# LCD-Battery.net
KiCad netlist of a schematic drawn in Altium Designer
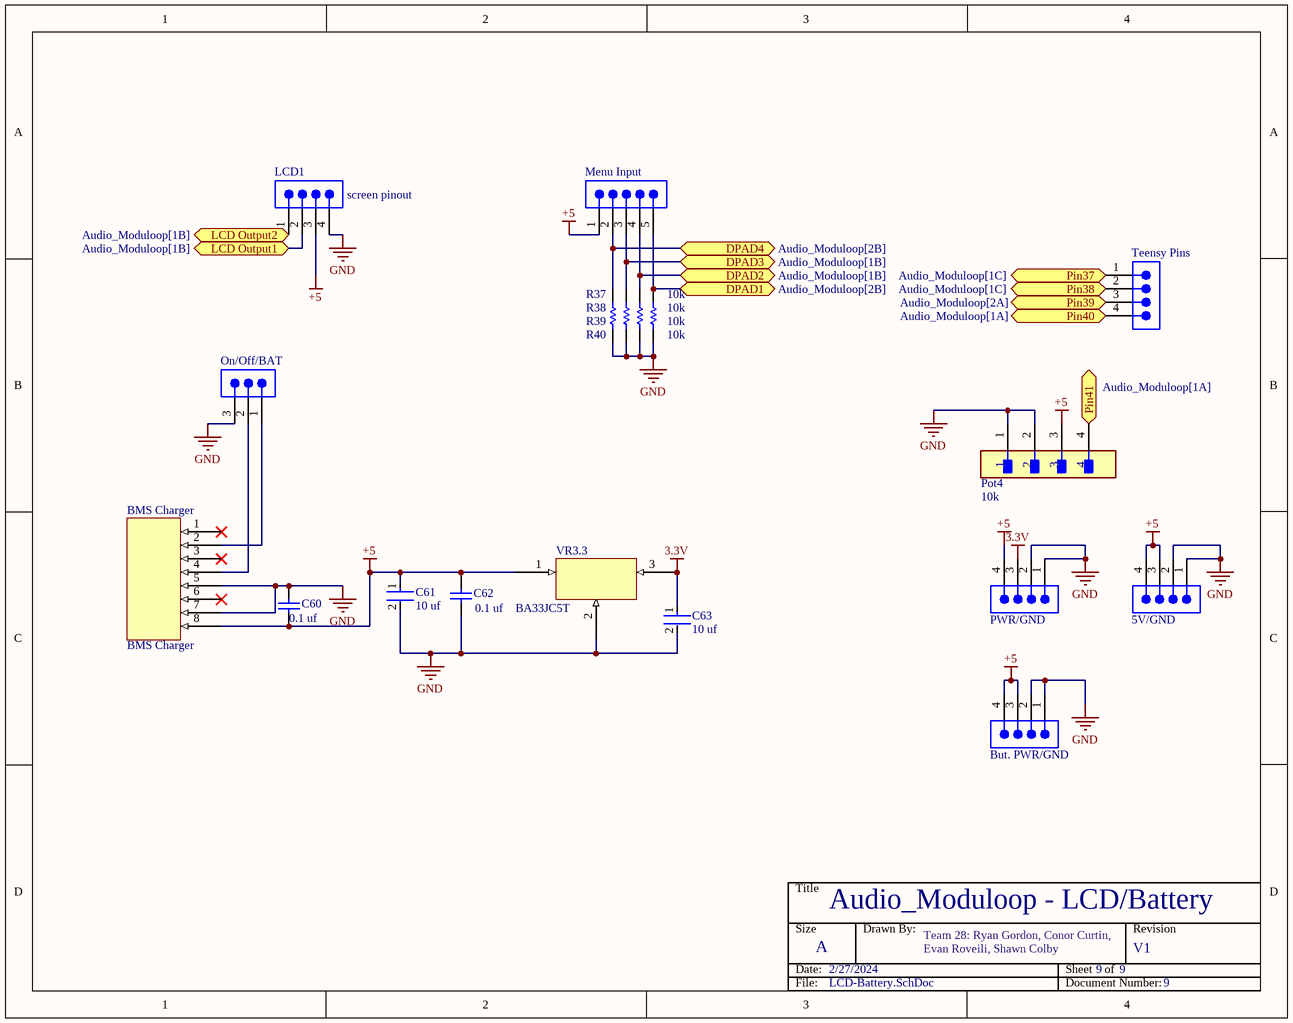
[diagram p0: LCD-Battery.SchDoc]

(export (version "E")
  (design (tool "Eeschema 10.0.6"))
  (components
    (comp (ref "5V/GND")
      (value "61300411121")
      (footprint "61300411121")
      (libsource (lib "Altium Content Vault") (part "Header_Male_1R_04P"))
    )
    (comp (ref "BMS Charger")
      (value "BMS Charger")
      (footprint "MODULE_2465")
      (description "Holder Battery; AA Battery; 3 Cells; 6 in. Wire Lead; Chassis Mount; Polypropylene")
      (libsource (lib "Ryamgordon") (part "Charger"))
    )
    (comp (ref "But. PWR/GND")
      (value "61300411121")
      (footprint "61300411121")
      (libsource (lib "Altium Content Vault") (part "Header_Male_1R_04P"))
    )
    (comp (ref "C60")
      (value "0.1 uf")
      (footprint "AVX-SA115C104KAR")
      (fields (field (name "TOLERANCE") "±10%") (field (name "MANUFACTURER") "AVX"))
      (libsource (lib "Altium Content Vault") (part "CAP-NP-2"))
    )
    (comp (ref "C61")
      (value "10 uf")
      (footprint "FP-RCE3DB-MFG")
      (description "Cap Ceramic 10uF 25V X7R ±10% Radial 2.5mm +125°C Automotive Ammo Pack")
      (fields (field (name "TOLERANCE") "10%"))
      (libsource (lib "Altium Content Vault") (part "b4654b650e69147ec39a6b967a45e02"))
    )
    (comp (ref "C62")
      (value "0.1 uf")
      (footprint "AVX-SA115C104KAR")
      (fields (field (name "TOLERANCE") "±10%") (field (name "MANUFACTURER") "AVX"))
      (libsource (lib "Altium Content Vault") (part "CAP-NP-2"))
    )
    (comp (ref "C63")
      (value "10 uf")
      (footprint "FP-RCE3DB-MFG")
      (description "Cap Ceramic 10uF 25V X7R ±10% Radial 2.5mm +125°C Automotive Ammo Pack")
      (fields (field (name "TOLERANCE") "10%"))
      (libsource (lib "Altium Content Vault") (part "b4654b650e69147ec39a6b967a45e02"))
    )
    (comp (ref "LCD1")
      (value "screen pinout")
      (footprint "61900411121")
      (libsource (lib "Altium Content Vault") (part "Header_Male_1R_04P"))
    )
    (comp (ref "Menu Input")
      (value "61300511121")
      (footprint "61300511121")
      (libsource (lib "Altium Content Vault") (part "Header_Male_1R_05P"))
    )
    (comp (ref "On/Off/BAT")
      (value "TSW-103-07-F-S")
      (footprint "SMTC-TSW-103-07-X-S")
      (description "0.025\" SQ Post Header, Through-hole, Vertical, -55 to 125 degC, 2.54 mm Pitch, 3-Pin, Male, RoHS")
      (fields (field (name "MANUFACTURER") "Samtec"))
      (libsource (lib "Altium Content Vault") (part "SMTC-TSW-103-X-X-S-X"))
    )
    (comp (ref "Pot4")
      (value "10k")
      (footprint "FP-B4B-XH-A_LF_SN-MFG")
      (description "CONN HEADER VERT 4POS 2.5MM")
      (libsource (lib "Altium Content Vault") (part "299a8cea1bdcbc3624fe62c390fa72c"))
    )
    (comp (ref "PWR/GND")
      (value "61300411121")
      (footprint "61300411121")
      (libsource (lib "Altium Content Vault") (part "Header_Male_1R_04P"))
    )
    (comp (ref "R37")
      (value "10k")
      (footprint "RESC2013X60X35NL10T20")
      (description "Chip Resistor, 10 KOhm, +/- 1%, 0.125 W, -55 to 155 degC, 0805 (2012 Metric), RoHS, Tape and Reel")
      (fields (field (name "MANUFACTURER") "Yageo"))
      (libsource (lib "Altium Content Vault") (part "RES-2"))
    )
    (comp (ref "R38")
      (value "10k")
      (footprint "RESC2013X60X35NL10T20")
      (description "Chip Resistor, 10 KOhm, +/- 1%, 0.125 W, -55 to 155 degC, 0805 (2012 Metric), RoHS, Tape and Reel")
      (fields (field (name "MANUFACTURER") "Yageo"))
      (libsource (lib "Altium Content Vault") (part "RES-2"))
    )
    (comp (ref "R39")
      (value "10k")
      (footprint "RESC2013X60X35NL10T20")
      (description "Chip Resistor, 10 KOhm, +/- 1%, 0.125 W, -55 to 155 degC, 0805 (2012 Metric), RoHS, Tape and Reel")
      (fields (field (name "MANUFACTURER") "Yageo"))
      (libsource (lib "Altium Content Vault") (part "RES-2"))
    )
    (comp (ref "R40")
      (value "10k")
      (footprint "RESC2013X60X35NL10T20")
      (description "Chip Resistor, 10 KOhm, +/- 1%, 0.125 W, -55 to 155 degC, 0805 (2012 Metric), RoHS, Tape and Reel")
      (fields (field (name "MANUFACTURER") "Yageo"))
      (libsource (lib "Altium Content Vault") (part "RES-2"))
    )
    (comp (ref "Teensy Pins")
      (value "61300411121")
      (footprint "61300411121")
      (libsource (lib "Altium Content Vault") (part "Header_Male_1R_04P"))
    )
    (comp (ref "VR3.3")
      (value "BA33JC5T")
      (footprint "TO254P1030X480X2260-3")
      (description "Fixed Positive LDO Regulator, 3.3V, 0.5V Dropout, BIPolar")
      (libsource (lib "Ryamgordon") (part "BA33JC5T-Symbol-1"))
    )
  )
  (nets
    (net (code "1") (name "+5") (class "Default")
      (node (ref "5V/GND") (pin "3") (pinfunction "3_3") (pintype "passive"))
      (node (ref "5V/GND") (pin "4") (pinfunction "4_4") (pintype "passive"))
      (node (ref "BMS Charger") (pin "8") (pintype "input"))
      (node (ref "But. PWR/GND") (pin "3") (pinfunction "3_3") (pintype "passive"))
      (node (ref "But. PWR/GND") (pin "4") (pinfunction "4_4") (pintype "passive"))
      (node (ref "C60") (pin "1") (pinfunction "1_1") (pintype "passive"))
      (node (ref "C61") (pin "1") (pinfunction "1_1") (pintype "passive"))
      (node (ref "C62") (pin "2") (pinfunction "2_2") (pintype "passive"))
      (node (ref "LCD1") (pin "3") (pinfunction "3_3") (pintype "passive"))
      (node (ref "Menu Input") (pin "1") (pinfunction "1_1") (pintype "passive"))
      (node (ref "PWR/GND") (pin "4") (pinfunction "4_4") (pintype "passive"))
      (node (ref "Pot4") (pin "3") (pinfunction "3_3") (pintype "passive"))
      (node (ref "VR3.3") (pin "1") (pintype "input"))
    )
    (net (code "2") (name "/DPAD1") (class "Default")
      (node (ref "Menu Input") (pin "5") (pinfunction "5_5") (pintype "passive"))
      (node (ref "R40") (pin "1") (pinfunction "1_1") (pintype "passive"))
    )
    (net (code "3") (name "/DPAD2") (class "Default")
      (node (ref "Menu Input") (pin "4") (pinfunction "4_4") (pintype "passive"))
      (node (ref "R39") (pin "1") (pinfunction "1_1") (pintype "passive"))
    )
    (net (code "4") (name "/DPAD3") (class "Default")
      (node (ref "Menu Input") (pin "3") (pinfunction "3_3") (pintype "passive"))
      (node (ref "R38") (pin "1") (pinfunction "1_1") (pintype "passive"))
    )
    (net (code "5") (name "/DPAD4") (class "Default")
      (node (ref "Menu Input") (pin "2") (pinfunction "2_2") (pintype "passive"))
      (node (ref "R37") (pin "1") (pinfunction "1_1") (pintype "passive"))
    )
    (net (code "6") (name "/LCD Output1") (class "Default")
      (node (ref "LCD1") (pin "2") (pinfunction "2_2") (pintype "passive"))
    )
    (net (code "7") (name "/LCD Output2") (class "Default")
      (node (ref "LCD1") (pin "1") (pinfunction "1_1") (pintype "passive"))
    )
    (net (code "8") (name "/Pin37") (class "Default")
      (node (ref "Teensy Pins") (pin "1") (pinfunction "1_1") (pintype "passive"))
    )
    (net (code "9") (name "/Pin38") (class "Default")
      (node (ref "Teensy Pins") (pin "2") (pinfunction "2_2") (pintype "passive"))
    )
    (net (code "10") (name "/Pin39") (class "Default")
      (node (ref "Teensy Pins") (pin "3") (pinfunction "3_3") (pintype "passive"))
    )
    (net (code "11") (name "/Pin40") (class "Default")
      (node (ref "Teensy Pins") (pin "4") (pinfunction "4_4") (pintype "passive"))
    )
    (net (code "12") (name "/Pin41") (class "Default")
      (node (ref "Pot4") (pin "4") (pinfunction "4_4") (pintype "passive"))
    )
    (net (code "13") (name "3.3V") (class "Default")
      (node (ref "C63") (pin "1") (pinfunction "1_1") (pintype "passive"))
      (node (ref "PWR/GND") (pin "3") (pinfunction "3_3") (pintype "passive"))
      (node (ref "VR3.3") (pin "3") (pintype "input"))
    )
    (net (code "14") (name "GND") (class "Default")
      (node (ref "5V/GND") (pin "1") (pinfunction "1_1") (pintype "passive"))
      (node (ref "5V/GND") (pin "2") (pinfunction "2_2") (pintype "passive"))
      (node (ref "BMS Charger") (pin "5") (pintype "input"))
      (node (ref "BMS Charger") (pin "7") (pintype "input"))
      (node (ref "But. PWR/GND") (pin "1") (pinfunction "1_1") (pintype "passive"))
      (node (ref "But. PWR/GND") (pin "2") (pinfunction "2_2") (pintype "passive"))
      (node (ref "C60") (pin "2") (pinfunction "2_2") (pintype "passive"))
      (node (ref "C61") (pin "2") (pinfunction "2_2") (pintype "passive"))
      (node (ref "C62") (pin "1") (pinfunction "1_1") (pintype "passive"))
      (node (ref "C63") (pin "2") (pinfunction "2_2") (pintype "passive"))
      (node (ref "LCD1") (pin "4") (pinfunction "4_4") (pintype "passive"))
      (node (ref "On/Off/BAT") (pin "3") (pinfunction "3_3") (pintype "passive"))
      (node (ref "PWR/GND") (pin "1") (pinfunction "1_1") (pintype "passive"))
      (node (ref "PWR/GND") (pin "2") (pinfunction "2_2") (pintype "passive"))
      (node (ref "Pot4") (pin "1") (pinfunction "1_1") (pintype "passive"))
      (node (ref "Pot4") (pin "2") (pinfunction "2_2") (pintype "passive"))
      (node (ref "R37") (pin "2") (pinfunction "2_2") (pintype "passive"))
      (node (ref "R38") (pin "2") (pinfunction "2_2") (pintype "passive"))
      (node (ref "R39") (pin "2") (pinfunction "2_2") (pintype "passive"))
      (node (ref "R40") (pin "2") (pinfunction "2_2") (pintype "passive"))
      (node (ref "VR3.3") (pin "2") (pintype "input"))
    )
    (net (code "15") (name "Net-(BMS Charger-Pad2)") (class "Default")
      (node (ref "BMS Charger") (pin "2") (pintype "input"))
      (node (ref "On/Off/BAT") (pin "1") (pinfunction "1_1") (pintype "passive"))
    )
    (net (code "16") (name "Net-(BMS Charger-Pad4)") (class "Default")
      (node (ref "BMS Charger") (pin "4") (pintype "input"))
      (node (ref "On/Off/BAT") (pin "2") (pinfunction "2_2") (pintype "passive"))
    )
    (net (code "17") (name "unconnected-(BMS Charger-Pad1)") (class "Default")
      (node (ref "BMS Charger") (pin "1") (pintype "input+no_connect"))
    )
    (net (code "18") (name "unconnected-(BMS Charger-Pad3)") (class "Default")
      (node (ref "BMS Charger") (pin "3") (pintype "input+no_connect"))
    )
    (net (code "19") (name "unconnected-(BMS Charger-Pad6)") (class "Default")
      (node (ref "BMS Charger") (pin "6") (pintype "input+no_connect"))
    )
  )
)
